# SH3_-_5V_BUCK_CONVERTER.net
KiCad netlist of a schematic drawn in Altium Designer
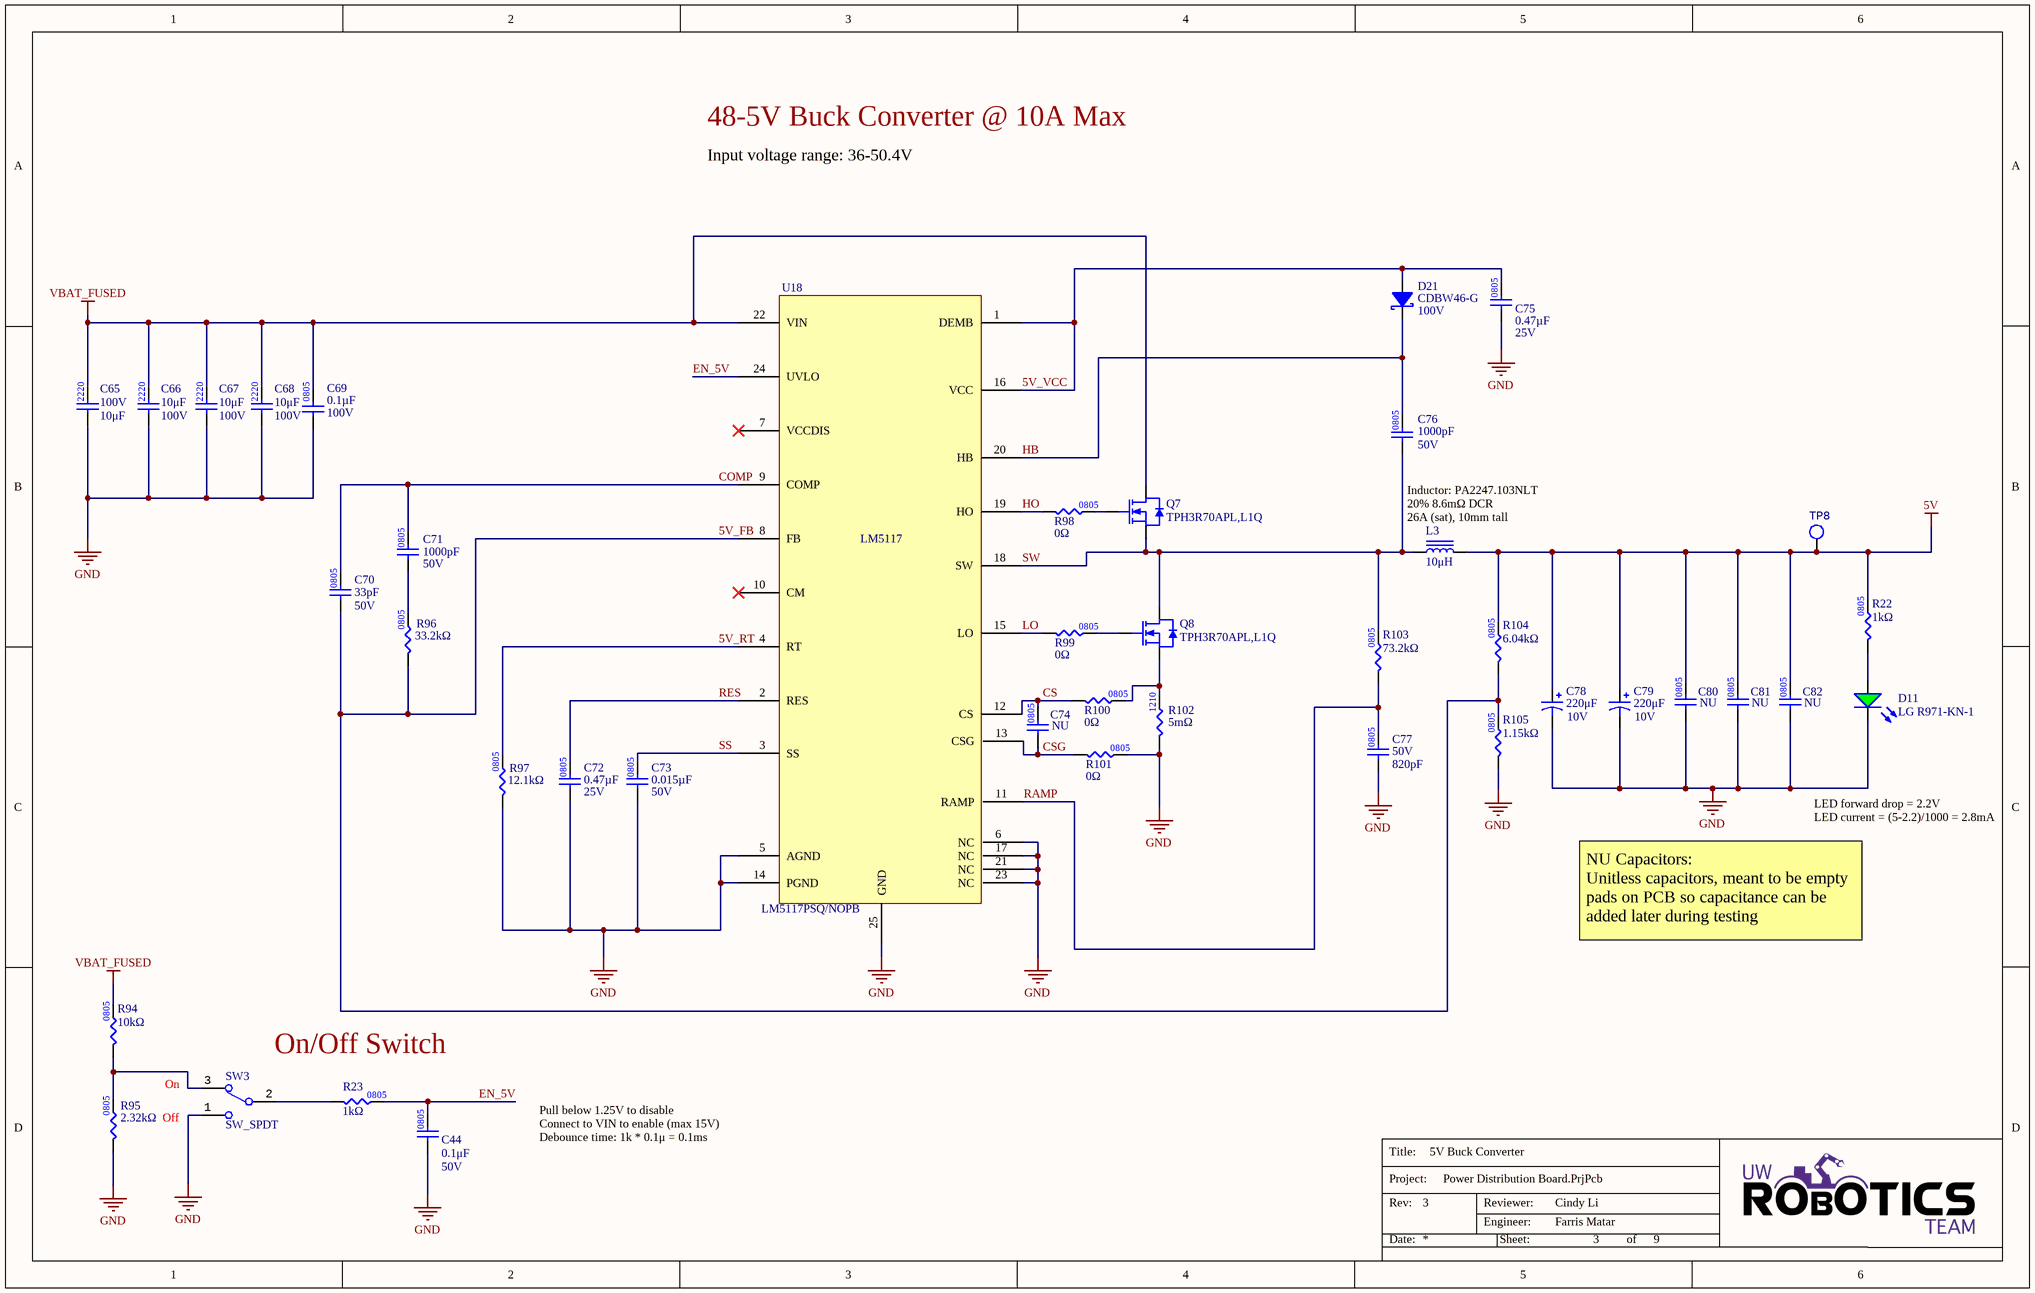
[diagram p0: SH3 - 5V BUCK CONVERTER.SchDoc]

(export (version "E")
  (design (tool "Eeschema 10.0.6"))
  (components
    (comp (ref "C44")
      (value "0.1μF")
      (footprint "CAP2012")
      (description "CAP CER 0.1UF 50V X7R 0805")
      (fields
        (field (name "VOLTAGE RATING") "50V")
        (field (name "LCSC PART #") "C49678")
        (field (name "Comment") "CAP_0.1uF_50V_0805")
      )
      (libsource (lib "UWRT_Schematic_Library_2020") (part "CAP_0.1uF_50V_0805"))
    )
    (comp (ref "C65")
      (value "10μF")
      (footprint "CAP2220")
      (description "CAP CER 10UF 100V X7S 2220")
      (fields (field (name "VOLTAGE RATING") "100V") (field (name "Comment") "CAP_10μF_100V_2220"))
      (libsource (lib "UWRT_Schematic_Library_2020") (part "CAP_10μF_100V_2220"))
    )
    (comp (ref "C66")
      (value "10μF")
      (footprint "CAP2220")
      (description "CAP CER 10UF 100V X7S 2220")
      (fields (field (name "VOLTAGE RATING") "100V") (field (name "Comment") "CAP_10μF_100V_2220"))
      (libsource (lib "UWRT_Schematic_Library_2020") (part "CAP_10μF_100V_2220"))
    )
    (comp (ref "C67")
      (value "10μF")
      (footprint "CAP2220")
      (description "CAP CER 10UF 100V X7S 2220")
      (fields (field (name "VOLTAGE RATING") "100V") (field (name "Comment") "CAP_10μF_100V_2220"))
      (libsource (lib "UWRT_Schematic_Library_2020") (part "CAP_10μF_100V_2220"))
    )
    (comp (ref "C68")
      (value "10μF")
      (footprint "CAP2220")
      (description "CAP CER 10UF 100V X7S 2220")
      (fields (field (name "VOLTAGE RATING") "100V") (field (name "Comment") "CAP_10μF_100V_2220"))
      (libsource (lib "UWRT_Schematic_Library_2020") (part "CAP_10μF_100V_2220"))
    )
    (comp (ref "C69")
      (value "0.1µF")
      (footprint "CAP0805")
      (description "CAP CER 0.1UF 100V X7R 0805")
      (fields (field (name "VOLTAGE RATING") "100V") (field (name "Comment") "CAP_0.1uF_100V_0805"))
      (libsource (lib "UWRT_Schematic_Library_2020") (part "CAP_0.1uF_100V_0805"))
    )
    (comp (ref "C70")
      (value "33pF")
      (footprint "CAP0805")
      (description "CAP CER 33PF 50V C0G/NP0 0805")
      (fields (field (name "VOLTAGE RATING") "50V") (field (name "Comment") "CAP_33pF_50V_0805"))
      (libsource (lib "UWRT_Schematic_Library_2020") (part "CAP_33pF_50V_0805"))
    )
    (comp (ref "C71")
      (value "1000pF")
      (footprint "CAP2012")
      (description "CAP CER 1000pF 50V X7R 0805")
      (fields (field (name "VOLTAGE RATING") "50V") (field (name "Comment") "CAP_1000pF_50V_0805"))
      (libsource (lib "UWRT_Schematic_Library_2020") (part "CAP_1000pF_50V_0805"))
    )
    (comp (ref "C72")
      (value "0.47µF")
      (footprint "CAP0805")
      (description "CAP CER 0.47UF 25V X5R 0805")
      (fields (field (name "VOLTAGE RATING") "25V") (field (name "Comment") "CAP_0.47uF_25V_0805"))
      (libsource (lib "UWRT_Schematic_Library_2020") (part "CAP_0.47uF_25V_0805"))
    )
    (comp (ref "C73")
      (value "0.015µF")
      (footprint "CAP0805")
      (description "CAP CER 0.015UF 50V C0G 0805")
      (fields (field (name "VOLTAGE RATING") "50V") (field (name "Comment") "CAP_0.015uF_50V_0805"))
      (libsource (lib "UWRT_Schematic_Library_2020") (part "CAP_0.015uF_50V_0805"))
    )
    (comp (ref "C74")
      (value "NU")
      (footprint "CAP0805")
      (description "PLACEHOLDER CAPACITOR")
      (fields (field (name "Comment") "CAP_NU_0805"))
      (libsource (lib "UWRT_Schematic_Library_2020") (part "CAP_NU_0805"))
    )
    (comp (ref "C75")
      (value "0.47µF")
      (footprint "CAP0805")
      (description "CAP CER 0.47UF 25V X5R 0805")
      (fields (field (name "VOLTAGE RATING") "25V") (field (name "Comment") "CAP_0.47uF_25V_0805"))
      (libsource (lib "UWRT_Schematic_Library_2020") (part "CAP_0.47uF_25V_0805"))
    )
    (comp (ref "C76")
      (value "1000pF")
      (footprint "CAP2012")
      (description "CAP CER 1000pF 50V X7R 0805")
      (fields (field (name "VOLTAGE RATING") "50V") (field (name "Comment") "CAP_1000pF_50V_0805"))
      (libsource (lib "UWRT_Schematic_Library_2020") (part "CAP_1000pF_50V_0805"))
    )
    (comp (ref "C77")
      (value "CAP_820pF_50V_0805")
      (footprint "CAP0805")
      (description "CAP CER 820PF 50V C0G/NP0 0805")
      (fields (field (name "VOLTAGE RATING") "50V") (field (name "CAPACITANCE") "820pF"))
      (libsource (lib "UWRT_Schematic_Library_2020") (part "CAP_820pF_50V_0805"))
    )
    (comp (ref "C78")
      (value "220μF")
      (footprint "CAP2917")
      (description "CAP TANT POLY 220UF 10V 2917")
      (fields (field (name "VOLTAGE RATING") "10V") (field (name "Comment") "CAP_220uF_10V_TANT"))
      (libsource (lib "UWRT_Schematic_Library_2020") (part "CAP_220uF_10V_TANT"))
    )
    (comp (ref "C79")
      (value "220μF")
      (footprint "CAP2917")
      (description "CAP TANT POLY 220UF 10V 2917")
      (fields (field (name "VOLTAGE RATING") "10V") (field (name "Comment") "CAP_220uF_10V_TANT"))
      (libsource (lib "UWRT_Schematic_Library_2020") (part "CAP_220uF_10V_TANT"))
    )
    (comp (ref "C80")
      (value "NU")
      (footprint "CAP0805")
      (description "PLACEHOLDER CAPACITOR")
      (fields (field (name "Comment") "CAP_NU_0805"))
      (libsource (lib "UWRT_Schematic_Library_2020") (part "CAP_NU_0805"))
    )
    (comp (ref "C81")
      (value "NU")
      (footprint "CAP0805")
      (description "PLACEHOLDER CAPACITOR")
      (fields (field (name "Comment") "CAP_NU_0805"))
      (libsource (lib "UWRT_Schematic_Library_2020") (part "CAP_NU_0805"))
    )
    (comp (ref "C82")
      (value "NU")
      (footprint "CAP0805")
      (description "PLACEHOLDER CAPACITOR")
      (fields (field (name "Comment") "CAP_NU_0805"))
      (libsource (lib "UWRT_Schematic_Library_2020") (part "CAP_NU_0805"))
    )
    (comp (ref "D11")
      (value "LED_GREEN")
      (footprint "LED_0805_GREEN")
      (description "LED GREEN DIFFUSED 0805 SMD")
      (fields (field (name "MANUFACTURER PART NUMBER 1") "LG R971-KN-1"))
      (libsource (lib "UWRT_Schematic_Library_2020") (part "LED_GREEN"))
    )
    (comp (ref "D21")
      (value "DIO_SCHOTTKY_100V_150mA")
      (footprint "SOD-123_FLAT")
      (description "DIODE SCHOTTKY 100V 150MA SOD123")
      (fields (field (name "MANUFACTURER PART NUMBER 1") "CDBW46-G") (field (name "VR (MAX)") "100V"))
      (libsource (lib "UWRT_Schematic_Library_2020") (part "DIO_SCHOTTKY_100V_150mA"))
    )
    (comp (ref "L3")
      (value "IND_10uH_24A")
      (footprint "IND_PULSE_PA2247")
      (description "FIXED IND 10UH 24A 8.6 MOHM SMD")
      (fields (field (name "INDUCTANCE") "10μH"))
      (libsource (lib "UWRT_Schematic_Library_2020") (part "IND_10uH_24A"))
    )
    (comp (ref "Q7")
      (value "NMOS_100V_90A")
      (footprint "8-SOP ADVANCE")
      (description "MOSFET N-CH 100V 90A 8SOP")
      (fields (field (name "MANUFACTURER PART NUMBER 1") "TPH3R70APL,L1Q"))
      (libsource (lib "UWRT_Schematic_Library_2020") (part "NMOS_100V_90A"))
    )
    (comp (ref "Q8")
      (value "NMOS_100V_90A")
      (footprint "8-SOP ADVANCE")
      (description "MOSFET N-CH 100V 90A 8SOP")
      (fields (field (name "MANUFACTURER PART NUMBER 1") "TPH3R70APL,L1Q"))
      (libsource (lib "UWRT_Schematic_Library_2020") (part "NMOS_100V_90A"))
    )
    (comp (ref "R22")
      (value "1kΩ")
      (footprint "RES0805")
      (description "RES 1K OHM 1% 1/8W 0805")
      (fields (field (name "LCSC PART #") "C17513") (field (name "Comment") "RES_1kΩ_0805_1%_1"))
      (libsource (lib "UWRT_Schematic_Library_2020") (part "RES_1kΩ_0805_1%_1"))
    )
    (comp (ref "R23")
      (value "1kΩ")
      (footprint "RES0805")
      (description "RES 1K OHM 1% 1/8W 0805")
      (fields (field (name "LCSC PART #") "C17513") (field (name "Comment") "RES_1kΩ_0805_1%"))
      (libsource (lib "UWRT_Schematic_Library_2020") (part "RES_1kΩ_0805_1%"))
    )
    (comp (ref "R94")
      (value "10kΩ")
      (footprint "RES0805")
      (description "RES 10K OHM 5% 1/8W 0805")
      (fields (field (name "LCSC PART #") "C17414") (field (name "Comment") "RES_10kΩ_0805_5%"))
      (libsource (lib "UWRT_Schematic_Library_2020") (part "RES_10kΩ_0805_5%"))
    )
    (comp (ref "R95")
      (value "2.32kΩ")
      (footprint "RES0805")
      (description "RES 2.32K OHM 1% 1/4W 0805")
      (fields (field (name "Comment") "RES_2.32kΩ_0805_1%"))
      (libsource (lib "UWRT_Schematic_Library_2020") (part "RES_2.32kΩ_0805_1%"))
    )
    (comp (ref "R96")
      (value "33.2kΩ")
      (footprint "RES0603")
      (description "RES 33.2K OHM 1% 1/8W 0805")
      (fields (field (name "Comment") "RES_33.2kΩ_0805_1%"))
      (libsource (lib "PDB-Rev3-Symbols") (part "RES_33.2kΩ_0805_1%"))
    )
    (comp (ref "R97")
      (value "12.1kΩ")
      (footprint "RES0805")
      (description "RES 12.1K OHM 1% 1/4W 0805")
      (fields (field (name "Comment") "RES_12.1kΩ_0805_1%"))
      (libsource (lib "UWRT_Schematic_Library_2020") (part "RES_12.1kΩ_0805_1%"))
    )
    (comp (ref "R98")
      (value "0Ω")
      (footprint "RES0805")
      (description "RES 0 OHM JUMPER 1/8W 0805")
      (fields (field (name "LCSC PART #") "C17477") (field (name "Comment") "RES_0Ω_0805"))
      (libsource (lib "UWRT_Schematic_Library_2020") (part "RES_0Ω_0805"))
    )
    (comp (ref "R99")
      (value "0Ω")
      (footprint "RES0805")
      (description "RES 0 OHM JUMPER 1/8W 0805")
      (fields (field (name "LCSC PART #") "C17477") (field (name "Comment") "RES_0Ω_0805"))
      (libsource (lib "UWRT_Schematic_Library_2020") (part "RES_0Ω_0805"))
    )
    (comp (ref "R100")
      (value "0Ω")
      (footprint "RES0805")
      (description "RES 0 OHM JUMPER 1/8W 0805")
      (fields (field (name "LCSC PART #") "C17477") (field (name "Comment") "RES_0Ω_0805"))
      (libsource (lib "UWRT_Schematic_Library_2020") (part "RES_0Ω_0805"))
    )
    (comp (ref "R101")
      (value "0Ω")
      (footprint "RES0805")
      (description "RES 0 OHM JUMPER 1/8W 0805")
      (fields (field (name "LCSC PART #") "C17477") (field (name "Comment") "RES_0Ω_0805"))
      (libsource (lib "UWRT_Schematic_Library_2020") (part "RES_0Ω_0805"))
    )
    (comp (ref "R102")
      (value "5mΩ")
      (footprint "RES1210")
      (description "RES 0.005 OHM 1% 1W 1210")
      (fields (field (name "Comment") "RES_5mΩ_1210_1%"))
      (libsource (lib "UWRT_Schematic_Library_2020") (part "RES_5mΩ_1210_1%"))
    )
    (comp (ref "R103")
      (value "73.2kΩ")
      (footprint "RES0603")
      (description "RES 73.2K OHM 1% 1/8W 0805")
      (fields (field (name "Comment") "RES_73.2kΩ_0805_1%"))
      (libsource (lib "PDB-Rev3-Symbols") (part "RES_73.2kΩ_0805_1%"))
    )
    (comp (ref "R104")
      (value "6.04kΩ")
      (footprint "RES0805")
      (description "RES 6.04K OHM 1% 1/8W 0805")
      (fields (field (name "Comment") "RES_6.04kΩ_0805_1%"))
      (libsource (lib "UWRT_Schematic_Library_2020") (part "RES_6.04kΩ_0805_1%"))
    )
    (comp (ref "R105")
      (value "1.15kΩ")
      (footprint "RES0805")
      (description "RES 1.15K OHM 1% 1/8W 0805")
      (fields (field (name "Comment") "RES_1.15kΩ_0805_1%"))
      (libsource (lib "UWRT_Schematic_Library_2020") (part "RES_1.15kΩ_0805_1%"))
    )
    (comp (ref "SW3")
      (value "SW_SPDT")
      (footprint "100SP1T1B4M2QE")
      (description "SWITCH TOGGLE SPDT 5A 120V")
      (libsource (lib "UWRT_Schematic_Library_2020") (part "SW_SPDT"))
    )
    (comp (ref "TP8")
      (value "TESTPOINT_LOOP")
      (footprint "TESTPOINT_LOOP")
      (description "TESTPOINT THRUHOLE")
      (libsource (lib "UWRT_Schematic_Library_2020") (part "TESTPOINT_LOOP"))
    )
    (comp (ref "U18")
      (value "BUCK_LM5117QFN")
      (footprint "24-WQFN")
      (description "IC REG CTRLR BUCK 24WQFN")
      (fields (field (name "MANUFACTURER PART NUMBER 1") "LM5117PSQ/NOPB"))
      (libsource (lib "UWRT_Schematic_Library_2020") (part "BUCK_LM5117QFN"))
    )
  )
  (nets
    (net (code "1") (name "/5V_FB") (class "Default")
      (node (ref "C70") (pin "1") (pinfunction "1_1") (pintype "passive"))
      (node (ref "R104") (pin "1") (pinfunction "1_1") (pintype "passive"))
      (node (ref "R105") (pin "2") (pinfunction "2_2") (pintype "passive"))
      (node (ref "R96") (pin "1") (pinfunction "1_1") (pintype "passive"))
      (node (ref "U18") (pin "8") (pinfunction "FB_8") (pintype "passive"))
    )
    (net (code "2") (name "/5V_RT") (class "Default")
      (node (ref "R97") (pin "2") (pinfunction "2_2") (pintype "passive"))
      (node (ref "U18") (pin "4") (pinfunction "RT_4") (pintype "passive"))
    )
    (net (code "3") (name "/5V_VCC") (class "Default")
      (node (ref "C75") (pin "2") (pinfunction "2_2") (pintype "passive"))
      (node (ref "D21") (pin "2") (pinfunction "Anode_2") (pintype "passive"))
      (node (ref "U18") (pin "1") (pinfunction "DEMB_1") (pintype "passive"))
      (node (ref "U18") (pin "16") (pinfunction "VCC_16") (pintype "passive"))
    )
    (net (code "4") (name "/COMP") (class "Default")
      (node (ref "C70") (pin "2") (pinfunction "2_2") (pintype "passive"))
      (node (ref "C71") (pin "2") (pinfunction "2_2") (pintype "passive"))
      (node (ref "U18") (pin "9") (pinfunction "COMP_9") (pintype "passive"))
    )
    (net (code "5") (name "/CS") (class "Default")
      (node (ref "C74") (pin "2") (pinfunction "2_2") (pintype "passive"))
      (node (ref "R100") (pin "1") (pinfunction "1_1") (pintype "passive"))
      (node (ref "U18") (pin "12") (pinfunction "CS_12") (pintype "passive"))
    )
    (net (code "6") (name "/CSG") (class "Default")
      (node (ref "C74") (pin "1") (pinfunction "1_1") (pintype "passive"))
      (node (ref "R101") (pin "1") (pinfunction "1_1") (pintype "passive"))
      (node (ref "U18") (pin "13") (pinfunction "CSG_13") (pintype "passive"))
    )
    (net (code "7") (name "/EN_5V") (class "Default")
      (node (ref "C44") (pin "2") (pinfunction "2_2") (pintype "passive"))
      (node (ref "R23") (pin "2") (pinfunction "2_2") (pintype "passive"))
      (node (ref "U18") (pin "24") (pinfunction "UVLO_24") (pintype "passive"))
    )
    (net (code "8") (name "/HB") (class "Default")
      (node (ref "C76") (pin "2") (pinfunction "2_2") (pintype "passive"))
      (node (ref "D21") (pin "1") (pinfunction "Cathode_1") (pintype "passive"))
      (node (ref "U18") (pin "20") (pinfunction "HB_20") (pintype "passive"))
    )
    (net (code "9") (name "/HO") (class "Default")
      (node (ref "R98") (pin "1") (pinfunction "1_1") (pintype "passive"))
      (node (ref "U18") (pin "19") (pinfunction "HO_19") (pintype "passive"))
    )
    (net (code "10") (name "/LO") (class "Default")
      (node (ref "R99") (pin "1") (pinfunction "1_1") (pintype "passive"))
      (node (ref "U18") (pin "15") (pinfunction "LO_15") (pintype "passive"))
    )
    (net (code "11") (name "/RAMP") (class "Default")
      (node (ref "C77") (pin "2") (pinfunction "2_2") (pintype "passive"))
      (node (ref "R103") (pin "1") (pinfunction "1_1") (pintype "passive"))
      (node (ref "U18") (pin "11") (pinfunction "RAMP_11") (pintype "passive"))
    )
    (net (code "12") (name "/RES") (class "Default")
      (node (ref "C72") (pin "2") (pinfunction "2_2") (pintype "passive"))
      (node (ref "U18") (pin "2") (pinfunction "RES_2") (pintype "passive"))
    )
    (net (code "13") (name "/SS") (class "Default")
      (node (ref "C73") (pin "2") (pinfunction "2_2") (pintype "passive"))
      (node (ref "U18") (pin "3") (pinfunction "SS_3") (pintype "passive"))
    )
    (net (code "14") (name "/SW") (class "Default")
      (node (ref "C76") (pin "1") (pinfunction "1_1") (pintype "passive"))
      (node (ref "L3") (pin "1") (pinfunction "1_1") (pintype "passive"))
      (node (ref "Q7") (pin "2") (pinfunction "Source_2") (pintype "passive"))
      (node (ref "Q8") (pin "3") (pinfunction "Drain_3") (pintype "passive"))
      (node (ref "R103") (pin "2") (pinfunction "2_2") (pintype "passive"))
      (node (ref "U18") (pin "18") (pinfunction "SW_18") (pintype "passive"))
    )
    (net (code "15") (name "5V") (class "Default")
      (node (ref "C78") (pin "1") (pinfunction "1_1") (pintype "passive"))
      (node (ref "C79") (pin "1") (pinfunction "1_1") (pintype "passive"))
      (node (ref "C80") (pin "2") (pinfunction "2_2") (pintype "passive"))
      (node (ref "C81") (pin "2") (pinfunction "2_2") (pintype "passive"))
      (node (ref "C82") (pin "2") (pinfunction "2_2") (pintype "passive"))
      (node (ref "L3") (pin "2") (pinfunction "2_2") (pintype "passive"))
      (node (ref "R104") (pin "2") (pinfunction "2_2") (pintype "passive"))
      (node (ref "R22") (pin "2") (pinfunction "2_2") (pintype "passive"))
      (node (ref "TP8") (pin "1") (pintype "passive"))
    )
    (net (code "16") (name "GND") (class "Default")
      (node (ref "C44") (pin "1") (pinfunction "1_1") (pintype "passive"))
      (node (ref "C65") (pin "1") (pinfunction "1_1") (pintype "passive"))
      (node (ref "C66") (pin "1") (pinfunction "1_1") (pintype "passive"))
      (node (ref "C67") (pin "1") (pinfunction "1_1") (pintype "passive"))
      (node (ref "C68") (pin "1") (pinfunction "1_1") (pintype "passive"))
      (node (ref "C69") (pin "1") (pinfunction "1_1") (pintype "passive"))
      (node (ref "C72") (pin "1") (pinfunction "1_1") (pintype "passive"))
      (node (ref "C73") (pin "1") (pinfunction "1_1") (pintype "passive"))
      (node (ref "C75") (pin "1") (pinfunction "1_1") (pintype "passive"))
      (node (ref "C77") (pin "1") (pinfunction "1_1") (pintype "passive"))
      (node (ref "C78") (pin "2") (pinfunction "2_2") (pintype "passive"))
      (node (ref "C79") (pin "2") (pinfunction "2_2") (pintype "passive"))
      (node (ref "C80") (pin "1") (pinfunction "1_1") (pintype "passive"))
      (node (ref "C81") (pin "1") (pinfunction "1_1") (pintype "passive"))
      (node (ref "C82") (pin "1") (pinfunction "1_1") (pintype "passive"))
      (node (ref "D11") (pin "2") (pinfunction "K_2") (pintype "passive"))
      (node (ref "R101") (pin "2") (pinfunction "2_2") (pintype "passive"))
      (node (ref "R102") (pin "1") (pinfunction "1_1") (pintype "passive"))
      (node (ref "R105") (pin "1") (pinfunction "1_1") (pintype "passive"))
      (node (ref "R95") (pin "1") (pinfunction "1_1") (pintype "passive"))
      (node (ref "R97") (pin "1") (pinfunction "1_1") (pintype "passive"))
      (node (ref "SW3") (pin "1") (pinfunction "1_1") (pintype "passive"))
      (node (ref "U18") (pin "14") (pinfunction "PGND_14") (pintype "passive"))
      (node (ref "U18") (pin "17") (pinfunction "NC_17") (pintype "passive"))
      (node (ref "U18") (pin "21") (pinfunction "NC_21") (pintype "passive"))
      (node (ref "U18") (pin "23") (pinfunction "NC_23") (pintype "passive"))
      (node (ref "U18") (pin "25") (pinfunction "GND_25") (pintype "passive"))
      (node (ref "U18") (pin "5") (pinfunction "AGND_5") (pintype "passive"))
      (node (ref "U18") (pin "6") (pinfunction "NC_6") (pintype "passive"))
    )
    (net (code "17") (name "Net-(C71-Pad1)") (class "Default")
      (node (ref "C71") (pin "1") (pinfunction "1_1") (pintype "passive"))
      (node (ref "R96") (pin "2") (pinfunction "2_2") (pintype "passive"))
    )
    (net (code "18") (name "Net-(D11-A)") (class "Default")
      (node (ref "D11") (pin "1") (pinfunction "A_1") (pintype "passive"))
      (node (ref "R22") (pin "1") (pinfunction "1_1") (pintype "passive"))
    )
    (net (code "19") (name "Net-(Q7-Gate)") (class "Default")
      (node (ref "Q7") (pin "1") (pinfunction "Gate_1") (pintype "passive"))
      (node (ref "R98") (pin "2") (pinfunction "2_2") (pintype "passive"))
    )
    (net (code "20") (name "Net-(Q8-Gate)") (class "Default")
      (node (ref "Q8") (pin "1") (pinfunction "Gate_1") (pintype "passive"))
      (node (ref "R99") (pin "2") (pinfunction "2_2") (pintype "passive"))
    )
    (net (code "21") (name "Net-(Q8-Source)") (class "Default")
      (node (ref "Q8") (pin "2") (pinfunction "Source_2") (pintype "passive"))
      (node (ref "R100") (pin "2") (pinfunction "2_2") (pintype "passive"))
      (node (ref "R102") (pin "2") (pinfunction "2_2") (pintype "passive"))
    )
    (net (code "22") (name "Net-(R23-Pad1)") (class "Default")
      (node (ref "R23") (pin "1") (pinfunction "1_1") (pintype "passive"))
      (node (ref "SW3") (pin "2") (pinfunction "2_2") (pintype "passive"))
    )
    (net (code "23") (name "Net-(R94-Pad1)") (class "Default")
      (node (ref "R94") (pin "1") (pinfunction "1_1") (pintype "passive"))
      (node (ref "R95") (pin "2") (pinfunction "2_2") (pintype "passive"))
      (node (ref "SW3") (pin "3") (pinfunction "3_3") (pintype "passive"))
    )
    (net (code "24") (name "VBAT_FUSED") (class "Default")
      (node (ref "C65") (pin "2") (pinfunction "2_2") (pintype "passive"))
      (node (ref "C66") (pin "2") (pinfunction "2_2") (pintype "passive"))
      (node (ref "C67") (pin "2") (pinfunction "2_2") (pintype "passive"))
      (node (ref "C68") (pin "2") (pinfunction "2_2") (pintype "passive"))
      (node (ref "C69") (pin "2") (pinfunction "2_2") (pintype "passive"))
      (node (ref "Q7") (pin "3") (pinfunction "Drain_3") (pintype "passive"))
      (node (ref "R94") (pin "2") (pinfunction "2_2") (pintype "passive"))
      (node (ref "U18") (pin "22") (pinfunction "VIN_22") (pintype "passive"))
    )
    (net (code "25") (name "unconnected-(U18-CM-Pad10)") (class "Default")
      (node (ref "U18") (pin "10") (pinfunction "CM_10") (pintype "passive+no_connect"))
    )
    (net (code "26") (name "unconnected-(U18-VCCDIS-Pad7)") (class "Default")
      (node (ref "U18") (pin "7") (pinfunction "VCCDIS_7") (pintype "passive+no_connect"))
    )
  )
)
